# MAIN_SCH.net
KiCad netlist of a schematic drawn in Altium Designer
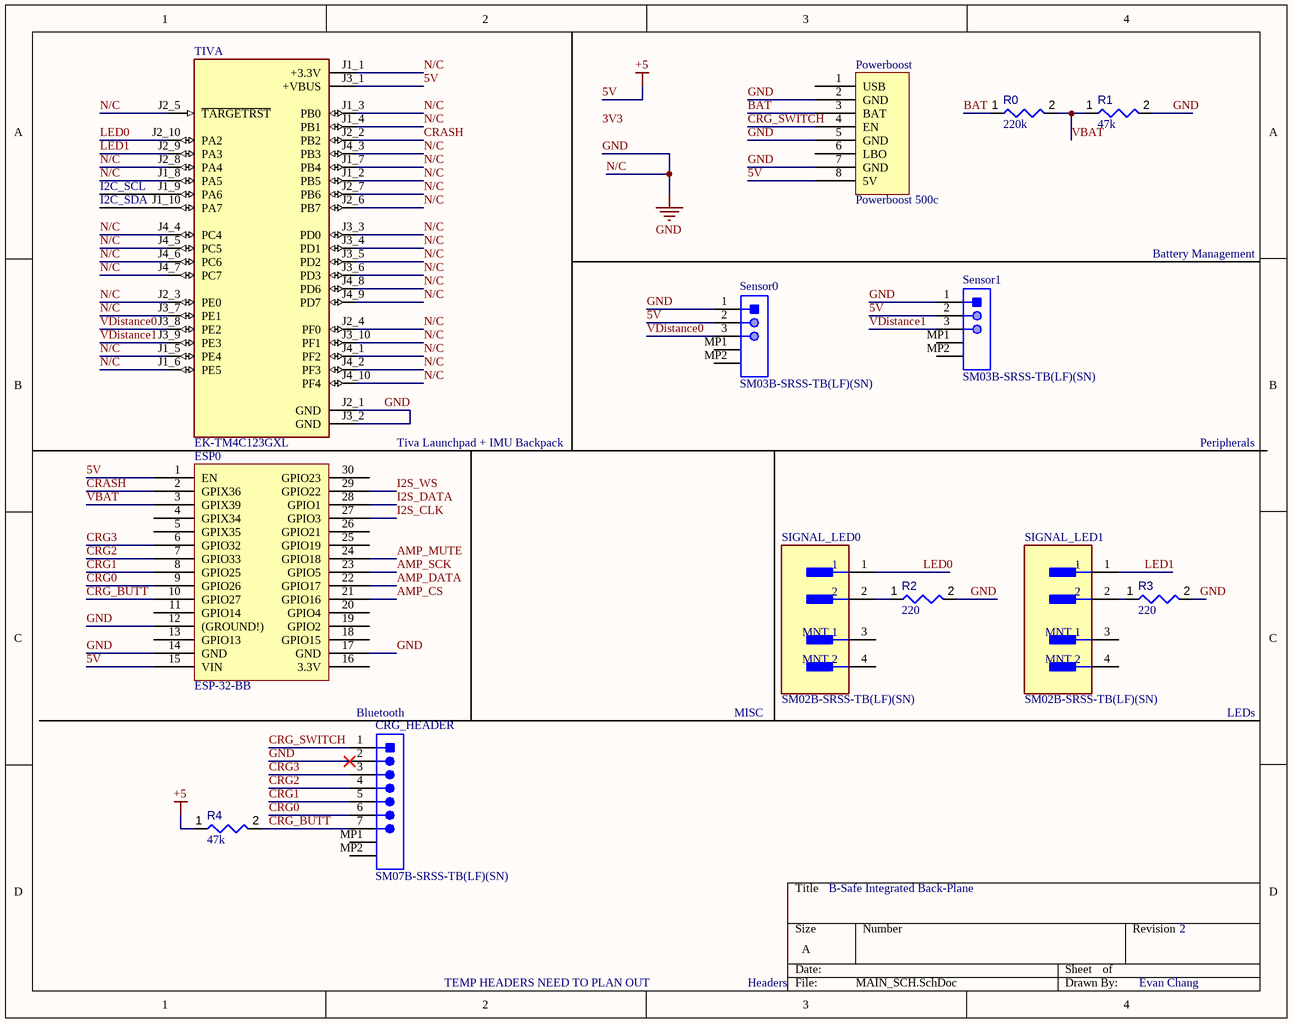
[diagram p0: MAIN_SCH.SchDoc]

(export (version "E")
  (design (tool "Eeschema 10.0.6"))
  (components
    (comp (ref "CRG_HEADER")
      (value "SM07B-SRSS-TB(LF)(SN)")
      (footprint "JST-SM07B-SRSS-TB_V")
      (description "CONN HEADER SH 7POS SIDE 1MM TIN")
      (libsource (lib "Evan Chang work on PCB") (part "CN-1P-2M-R7"))
    )
    (comp (ref "ESP0")
      (value "ESP-32-BB")
      (footprint "ESP-32-BB-Footprint-1")
      (description "Breakoutboard for ESP-32-BB")
      (libsource (lib "Evan Chang work on PCB") (part "ESP-32-BB-Symbol-1"))
    )
    (comp (ref "Powerboost")
      (value "Powerboost 500c")
      (footprint "Powerboost 500c-Footprint-1")
      (description "Breakout board component for Adafruit Powerboost 500c")
      (libsource (lib "Evan Chang work on PCB") (part "Powerboost 500c-Symbol-1"))
    )
    (comp (ref "R0")
      (value "220k")
      (footprint "RESC1005X40X25NL05T10")
      (fields (field (name "TOLERANCE") "1%") (field (name "Comment") "RC0402FR-07220KL"))
      (libsource (lib "Evan Chang work on PCB") (part "RES-2"))
    )
    (comp (ref "R1")
      (value "47k")
      (footprint "RESC1005X40X25NL05T10")
      (fields (field (name "TOLERANCE") "1%") (field (name "Comment") "RC0402FR-0747KL"))
      (libsource (lib "Evan Chang work on PCB") (part "RES-2"))
    )
    (comp (ref "R2")
      (value "220")
      (footprint "RESC1608X55X30LL20T10")
      (fields (field (name "TOLERANCE") "5%") (field (name "Comment") "RK73B1JTTD221J"))
      (libsource (lib "Evan Chang work on PCB") (part "RES-2"))
    )
    (comp (ref "R3")
      (value "220")
      (footprint "RESC1608X55X30LL20T10")
      (fields (field (name "TOLERANCE") "5%") (field (name "Comment") "RK73B1JTTD221J"))
      (libsource (lib "Evan Chang work on PCB") (part "RES-2"))
    )
    (comp (ref "R4")
      (value "47k")
      (footprint "RESC1005X40X25NL05T10")
      (fields (field (name "TOLERANCE") "1%") (field (name "Comment") "RC0402FR-0747KL"))
      (libsource (lib "Evan Chang work on PCB") (part "RES-2"))
    )
    (comp (ref "Sensor0")
      (value "SM03B-SRSS-TB(LF)(SN)")
      (footprint "JST-SM03B-SRSS-TB_V")
      (description "CONN HEADER SH 3POS SIDE 1MM TIN")
      (libsource (lib "Evan Chang work on PCB") (part "CN-1P-2M-R3"))
    )
    (comp (ref "Sensor1")
      (value "SM03B-SRSS-TB(LF)(SN)")
      (footprint "JST-SM03B-SRSS-TB_V")
      (description "CONN HEADER SH 3POS SIDE 1MM TIN")
      (libsource (lib "Evan Chang work on PCB") (part "CN-1P-2M-R3"))
    )
    (comp (ref "SIGNAL_LED0")
      (value "SM02B-SRSS-TB(LF)(SN)")
      (footprint "FP-SM02B-SRSS-TB_LF_SN-0")
      (description "CONN HEADER SH 2POS SIDE 1MM TIN")
      (libsource (lib "Evan Chang work on PCB") (part "e34efe21362d63d7198b5d2c73e37bd"))
    )
    (comp (ref "SIGNAL_LED1")
      (value "SM02B-SRSS-TB(LF)(SN)")
      (footprint "FP-SM02B-SRSS-TB_LF_SN-0")
      (description "CONN HEADER SH 2POS SIDE 1MM TIN")
      (libsource (lib "Evan Chang work on PCB") (part "e34efe21362d63d7198b5d2c73e37bd"))
    )
    (comp (ref "TIVA")
      (value "EK-TM4C123GXL")
      (footprint "EK-TM4C123GXL-Footprint-1")
      (description "ARMÂ® CortexÂ®-M4F Based MCU TM4C123G LaunchPadâ„¢ Evaluation Kit")
      (fields (field (name "MF") "Texas Instruments"))
      (libsource (lib "Evan Chang work on PCB") (part "EK-TM4C123GXL"))
    )
  )
  (nets
    (net (code "1") (name "+5") (class "Default")
      (node (ref "ESP0") (pin "1") (pinfunction "EN_1") (pintype "passive"))
      (node (ref "ESP0") (pin "15") (pinfunction "VIN_15") (pintype "power_in"))
      (node (ref "Powerboost") (pin "8") (pinfunction "5V_8") (pintype "power_in"))
      (node (ref "R4") (pin "1") (pinfunction "1_1") (pintype "passive"))
      (node (ref "Sensor0") (pin "2") (pinfunction "2_2") (pintype "passive"))
      (node (ref "Sensor1") (pin "2") (pinfunction "2_2") (pintype "passive"))
      (node (ref "TIVA") (pin "J3_1") (pinfunction "+VBUS_J3_1") (pintype "power_in"))
    )
    (net (code "3") (name "/AMP_CS") (class "Default")
      (node (ref "ESP0") (pin "21") (pinfunction "GPIO16_21") (pintype "passive"))
    )
    (net (code "4") (name "/AMP_DATA") (class "Default")
      (node (ref "ESP0") (pin "22") (pinfunction "GPIO17_22") (pintype "passive"))
    )
    (net (code "5") (name "/AMP_MUTE") (class "Default")
      (node (ref "ESP0") (pin "24") (pinfunction "GPIO18_24") (pintype "passive"))
    )
    (net (code "6") (name "/AMP_SCK") (class "Default")
      (node (ref "ESP0") (pin "23") (pinfunction "GPIO5_23") (pintype "passive"))
    )
    (net (code "7") (name "/BAT") (class "Default")
      (node (ref "Powerboost") (pin "3") (pinfunction "BAT_3") (pintype "passive"))
      (node (ref "R0") (pin "1") (pinfunction "1_1") (pintype "passive"))
    )
    (net (code "8") (name "/CRASH") (class "Default")
      (node (ref "ESP0") (pin "2") (pinfunction "GPIX36_2") (pintype "passive"))
      (node (ref "TIVA") (pin "J2_2") (pinfunction "PB2_J2_2") (pintype "bidirectional"))
    )
    (net (code "9") (name "/CRG0") (class "Default")
      (node (ref "CRG_HEADER") (pin "6") (pinfunction "6_6") (pintype "passive"))
      (node (ref "ESP0") (pin "9") (pinfunction "GPIO26_9") (pintype "passive"))
    )
    (net (code "10") (name "/CRG1") (class "Default")
      (node (ref "CRG_HEADER") (pin "5") (pinfunction "5_5") (pintype "passive"))
      (node (ref "ESP0") (pin "8") (pinfunction "GPIO25_8") (pintype "passive"))
    )
    (net (code "11") (name "/CRG2") (class "Default")
      (node (ref "CRG_HEADER") (pin "4") (pinfunction "4_4") (pintype "passive"))
      (node (ref "ESP0") (pin "7") (pinfunction "GPIO33_7") (pintype "passive"))
    )
    (net (code "12") (name "/CRG3") (class "Default")
      (node (ref "CRG_HEADER") (pin "3") (pinfunction "3_3") (pintype "passive"))
      (node (ref "ESP0") (pin "6") (pinfunction "GPIO32_6") (pintype "passive"))
    )
    (net (code "13") (name "/CRG_BUTT") (class "Default")
      (node (ref "CRG_HEADER") (pin "7") (pinfunction "7_7") (pintype "passive"))
      (node (ref "ESP0") (pin "10") (pinfunction "GPIO27_10") (pintype "passive"))
      (node (ref "R4") (pin "2") (pinfunction "2_2") (pintype "passive"))
    )
    (net (code "14") (name "/CRG_SWITCH") (class "Default")
      (node (ref "CRG_HEADER") (pin "1") (pinfunction "1_1") (pintype "passive"))
      (node (ref "Powerboost") (pin "4") (pinfunction "EN_4") (pintype "passive"))
    )
    (net (code "15") (name "/I2S_CLK") (class "Default")
      (node (ref "ESP0") (pin "27") (pinfunction "GPIO3_27") (pintype "passive"))
    )
    (net (code "16") (name "/I2S_DATA") (class "Default")
      (node (ref "ESP0") (pin "28") (pinfunction "GPIO1_28") (pintype "passive"))
    )
    (net (code "17") (name "/I2S_WS") (class "Default")
      (node (ref "ESP0") (pin "29") (pinfunction "GPIO22_29") (pintype "passive"))
    )
    (net (code "18") (name "/LED0") (class "Default")
      (node (ref "SIGNAL_LED0") (pin "1") (pinfunction "1_1") (pintype "passive"))
      (node (ref "TIVA") (pin "J2_10") (pinfunction "PA2_J2_10") (pintype "bidirectional"))
    )
    (net (code "19") (name "/LED1") (class "Default")
      (node (ref "SIGNAL_LED1") (pin "1") (pinfunction "1_1") (pintype "passive"))
      (node (ref "TIVA") (pin "J2_9") (pinfunction "PA3_J2_9") (pintype "bidirectional"))
    )
    (net (code "20") (name "/VBAT") (class "Default")
      (node (ref "ESP0") (pin "3") (pinfunction "GPIX39_3") (pintype "passive"))
      (node (ref "R0") (pin "2") (pinfunction "2_2") (pintype "passive"))
      (node (ref "R1") (pin "1") (pinfunction "1_1") (pintype "passive"))
    )
    (net (code "21") (name "/VDistance0") (class "Default")
      (node (ref "Sensor0") (pin "3") (pinfunction "3_3") (pintype "passive"))
      (node (ref "TIVA") (pin "J3_8") (pinfunction "PE2_J3_8") (pintype "bidirectional"))
    )
    (net (code "22") (name "/VDistance1") (class "Default")
      (node (ref "Sensor1") (pin "3") (pinfunction "3_3") (pintype "passive"))
      (node (ref "TIVA") (pin "J3_9") (pinfunction "PE3_J3_9") (pintype "bidirectional"))
    )
    (net (code "23") (name "GND") (class "Default")
      (node (ref "CRG_HEADER") (pin "2") (pinfunction "2_2") (pintype "passive"))
      (node (ref "ESP0") (pin "12") (pinfunction "(GROUND!)_12") (pintype "passive"))
      (node (ref "ESP0") (pin "14") (pinfunction "GND_14") (pintype "power_in"))
      (node (ref "ESP0") (pin "17") (pinfunction "GND_17") (pintype "power_in"))
      (node (ref "Powerboost") (pin "2") (pinfunction "GND_2") (pintype "power_in"))
      (node (ref "Powerboost") (pin "5") (pinfunction "GND_5") (pintype "power_in"))
      (node (ref "Powerboost") (pin "7") (pinfunction "GND_7") (pintype "power_in"))
      (node (ref "R1") (pin "2") (pinfunction "2_2") (pintype "passive"))
      (node (ref "R2") (pin "2") (pinfunction "2_2") (pintype "passive"))
      (node (ref "R3") (pin "2") (pinfunction "2_2") (pintype "passive"))
      (node (ref "Sensor0") (pin "1") (pinfunction "1_1") (pintype "passive"))
      (node (ref "Sensor1") (pin "1") (pinfunction "1_1") (pintype "passive"))
      (node (ref "TIVA") (pin "J1_1") (pinfunction "+3.3V_J1_1") (pintype "power_in"))
      (node (ref "TIVA") (pin "J1_2") (pinfunction "PB5_J1_2") (pintype "bidirectional"))
      (node (ref "TIVA") (pin "J1_3") (pinfunction "PB0_J1_3") (pintype "bidirectional"))
      (node (ref "TIVA") (pin "J1_4") (pinfunction "PB1_J1_4") (pintype "bidirectional"))
      (node (ref "TIVA") (pin "J1_5") (pinfunction "PE4_J1_5") (pintype "bidirectional"))
      (node (ref "TIVA") (pin "J1_6") (pinfunction "PE5_J1_6") (pintype "bidirectional"))
      (node (ref "TIVA") (pin "J1_7") (pinfunction "PB4_J1_7") (pintype "bidirectional"))
      (node (ref "TIVA") (pin "J1_8") (pinfunction "PA5_J1_8") (pintype "bidirectional"))
      (node (ref "TIVA") (pin "J2_1") (pinfunction "GND_J2_1") (pintype "power_in"))
      (node (ref "TIVA") (pin "J2_3") (pinfunction "PE0_J2_3") (pintype "bidirectional"))
      (node (ref "TIVA") (pin "J2_4") (pinfunction "PF0_J2_4") (pintype "bidirectional"))
      (node (ref "TIVA") (pin "J2_5") (pinfunction "~{TARGETRST}_J2_5") (pintype "input"))
      (node (ref "TIVA") (pin "J2_6") (pinfunction "PB7_J2_6") (pintype "bidirectional"))
      (node (ref "TIVA") (pin "J2_7") (pinfunction "PB6_J2_7") (pintype "bidirectional"))
      (node (ref "TIVA") (pin "J2_8") (pinfunction "PA4_J2_8") (pintype "bidirectional"))
      (node (ref "TIVA") (pin "J3_10") (pinfunction "PF1_J3_10") (pintype "bidirectional"))
      (node (ref "TIVA") (pin "J3_2") (pinfunction "GND_J3_2") (pintype "power_in"))
      (node (ref "TIVA") (pin "J3_3") (pinfunction "PD0_J3_3") (pintype "bidirectional"))
      (node (ref "TIVA") (pin "J3_4") (pinfunction "PD1_J3_4") (pintype "bidirectional"))
      (node (ref "TIVA") (pin "J3_5") (pinfunction "PD2_J3_5") (pintype "bidirectional"))
      (node (ref "TIVA") (pin "J3_6") (pinfunction "PD3_J3_6") (pintype "bidirectional"))
      (node (ref "TIVA") (pin "J3_7") (pinfunction "PE1_J3_7") (pintype "bidirectional"))
      (node (ref "TIVA") (pin "J4_1") (pinfunction "PF2_J4_1") (pintype "bidirectional"))
      (node (ref "TIVA") (pin "J4_10") (pinfunction "PF4_J4_10") (pintype "bidirectional"))
      (node (ref "TIVA") (pin "J4_2") (pinfunction "PF3_J4_2") (pintype "bidirectional"))
      (node (ref "TIVA") (pin "J4_3") (pinfunction "PB3_J4_3") (pintype "bidirectional"))
      (node (ref "TIVA") (pin "J4_4") (pinfunction "PC4_J4_4") (pintype "bidirectional"))
      (node (ref "TIVA") (pin "J4_5") (pinfunction "PC5_J4_5") (pintype "bidirectional"))
      (node (ref "TIVA") (pin "J4_6") (pinfunction "PC6_J4_6") (pintype "bidirectional"))
      (node (ref "TIVA") (pin "J4_7") (pinfunction "PC7_J4_7") (pintype "bidirectional"))
      (node (ref "TIVA") (pin "J4_8") (pinfunction "PD6_J4_8") (pintype "bidirectional"))
      (node (ref "TIVA") (pin "J4_9") (pinfunction "PD7_J4_9") (pintype "bidirectional"))
    )
    (net (code "24") (name "Net-(R2-Pad1)") (class "Default")
      (node (ref "R2") (pin "1") (pinfunction "1_1") (pintype "passive"))
      (node (ref "SIGNAL_LED0") (pin "2") (pinfunction "2_2") (pintype "passive"))
    )
    (net (code "25") (name "Net-(R3-Pad1)") (class "Default")
      (node (ref "R3") (pin "1") (pinfunction "1_1") (pintype "passive"))
      (node (ref "SIGNAL_LED1") (pin "2") (pinfunction "2_2") (pintype "passive"))
    )
    (net (code "26") (name "unconnected-(CRG_HEADER-PadMP1)") (class "Default")
      (node (ref "CRG_HEADER") (pin "MP1") (pinfunction "MP1_MP1") (pintype "passive"))
    )
    (net (code "27") (name "unconnected-(CRG_HEADER-PadMP2)") (class "Default")
      (node (ref "CRG_HEADER") (pin "MP2") (pinfunction "MP2_MP2") (pintype "passive"))
    )
    (net (code "28") (name "unconnected-(ESP0-3.3V-Pad16)") (class "Default")
      (node (ref "ESP0") (pin "16") (pinfunction "3.3V_16") (pintype "passive"))
    )
    (net (code "29") (name "unconnected-(ESP0-GPIO2-Pad19)") (class "Default")
      (node (ref "ESP0") (pin "19") (pinfunction "GPIO2_19") (pintype "passive"))
    )
    (net (code "30") (name "unconnected-(ESP0-GPIO4-Pad20)") (class "Default")
      (node (ref "ESP0") (pin "20") (pinfunction "GPIO4_20") (pintype "passive"))
    )
    (net (code "31") (name "unconnected-(ESP0-GPIO13-Pad13)") (class "Default")
      (node (ref "ESP0") (pin "13") (pinfunction "GPIO13_13") (pintype "passive"))
    )
    (net (code "32") (name "unconnected-(ESP0-GPIO14-Pad11)") (class "Default")
      (node (ref "ESP0") (pin "11") (pinfunction "GPIO14_11") (pintype "passive"))
    )
    (net (code "33") (name "unconnected-(ESP0-GPIO15-Pad18)") (class "Default")
      (node (ref "ESP0") (pin "18") (pinfunction "GPIO15_18") (pintype "passive"))
    )
    (net (code "34") (name "unconnected-(ESP0-GPIO19-Pad25)") (class "Default")
      (node (ref "ESP0") (pin "25") (pinfunction "GPIO19_25") (pintype "passive"))
    )
    (net (code "35") (name "unconnected-(ESP0-GPIO21-Pad26)") (class "Default")
      (node (ref "ESP0") (pin "26") (pinfunction "GPIO21_26") (pintype "passive"))
    )
    (net (code "36") (name "unconnected-(ESP0-GPIO23-Pad30)") (class "Default")
      (node (ref "ESP0") (pin "30") (pinfunction "GPIO23_30") (pintype "passive"))
    )
    (net (code "37") (name "unconnected-(ESP0-GPIX34-Pad4)") (class "Default")
      (node (ref "ESP0") (pin "4") (pinfunction "GPIX34_4") (pintype "passive"))
    )
    (net (code "38") (name "unconnected-(ESP0-GPIX35-Pad5)") (class "Default")
      (node (ref "ESP0") (pin "5") (pinfunction "GPIX35_5") (pintype "passive"))
    )
    (net (code "39") (name "unconnected-(Powerboost-LBO-Pad6)") (class "Default")
      (node (ref "Powerboost") (pin "6") (pinfunction "LBO_6") (pintype "passive"))
    )
    (net (code "40") (name "unconnected-(Powerboost-USB-Pad1)") (class "Default")
      (node (ref "Powerboost") (pin "1") (pinfunction "USB_1") (pintype "passive"))
    )
    (net (code "41") (name "unconnected-(SIGNAL_LED0-MNT_1-Pad3)") (class "Default")
      (node (ref "SIGNAL_LED0") (pin "3") (pinfunction "MNT_1_3") (pintype "passive"))
    )
    (net (code "42") (name "unconnected-(SIGNAL_LED0-MNT_2-Pad4)") (class "Default")
      (node (ref "SIGNAL_LED0") (pin "4") (pinfunction "MNT_2_4") (pintype "passive"))
    )
    (net (code "43") (name "unconnected-(SIGNAL_LED1-MNT_1-Pad3)") (class "Default")
      (node (ref "SIGNAL_LED1") (pin "3") (pinfunction "MNT_1_3") (pintype "passive"))
    )
    (net (code "44") (name "unconnected-(SIGNAL_LED1-MNT_2-Pad4)") (class "Default")
      (node (ref "SIGNAL_LED1") (pin "4") (pinfunction "MNT_2_4") (pintype "passive"))
    )
    (net (code "45") (name "unconnected-(Sensor0-PadMP1)") (class "Default")
      (node (ref "Sensor0") (pin "MP1") (pinfunction "MP1_MP1") (pintype "passive"))
    )
    (net (code "46") (name "unconnected-(Sensor0-PadMP2)") (class "Default")
      (node (ref "Sensor0") (pin "MP2") (pinfunction "MP2_MP2") (pintype "passive"))
    )
    (net (code "47") (name "unconnected-(Sensor1-PadMP1)") (class "Default")
      (node (ref "Sensor1") (pin "MP1") (pinfunction "MP1_MP1") (pintype "passive"))
    )
    (net (code "48") (name "unconnected-(Sensor1-PadMP2)") (class "Default")
      (node (ref "Sensor1") (pin "MP2") (pinfunction "MP2_MP2") (pintype "passive"))
    )
    (net (code "49") (name "unconnected-(TIVA-PA6-PadJ1_9)") (class "Default")
      (node (ref "TIVA") (pin "J1_9") (pinfunction "PA6_J1_9") (pintype "bidirectional"))
    )
    (net (code "50") (name "unconnected-(TIVA-PA7-PadJ1_10)") (class "Default")
      (node (ref "TIVA") (pin "J1_10") (pinfunction "PA7_J1_10") (pintype "bidirectional"))
    )
  )
)
